# Webasto_X250_3.net
KiCad netlist of a schematic drawn in EAGLE
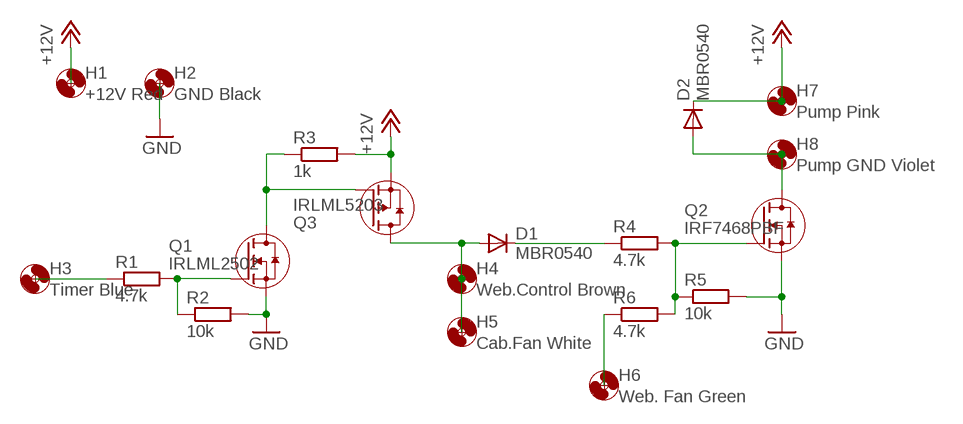
[diagram p0: schematic, sheet 1]

(export (version "E")
  (design (tool "Eeschema 10.0.6"))
  (components
    (comp (ref "D1")
      (value "MBR0540")
      (footprint "eagle-import:SOD-123_MINI-SMA")
      (libsource (lib "eagle-import") (part "CGRM400-G1"))
    )
    (comp (ref "D2")
      (value "MBR0540")
      (footprint "eagle-import:SOD-123_MINI-SMA")
      (libsource (lib "eagle-import") (part "CGRM400-G1"))
    )
    (comp (ref "H1")
      (value "+12V Red")
      (footprint "eagle-import:3,6")
      (libsource (lib "eagle-import") (part "MOUNT-HOLE3.6"))
    )
    (comp (ref "H2")
      (value "GND Black")
      (footprint "eagle-import:3,6")
      (libsource (lib "eagle-import") (part "MOUNT-HOLE3.6"))
    )
    (comp (ref "H3")
      (value "Timer Blue")
      (footprint "eagle-import:3,6")
      (libsource (lib "eagle-import") (part "MOUNT-HOLE3.6"))
    )
    (comp (ref "H4")
      (value "Web.Control Brown")
      (footprint "eagle-import:3,6")
      (libsource (lib "eagle-import") (part "MOUNT-HOLE3.6"))
    )
    (comp (ref "H5")
      (value "Cab.Fan White")
      (footprint "eagle-import:3,6")
      (libsource (lib "eagle-import") (part "MOUNT-HOLE3.6"))
    )
    (comp (ref "H6")
      (value "Web. Fan Green")
      (footprint "eagle-import:3,6")
      (libsource (lib "eagle-import") (part "MOUNT-HOLE3.6"))
    )
    (comp (ref "H7")
      (value "Pump Pink")
      (footprint "eagle-import:3,6")
      (libsource (lib "eagle-import") (part "MOUNT-HOLE3.6"))
    )
    (comp (ref "H8")
      (value "Pump GND Violet")
      (footprint "eagle-import:3,6")
      (libsource (lib "eagle-import") (part "MOUNT-HOLE3.6"))
    )
    (comp (ref "Q1")
      (value "IRLML2502")
      (footprint "eagle-import:SOT-23-GSD")
      (libsource (lib "eagle-import") (part "SI2302"))
    )
    (comp (ref "Q2")
      (value "IRF7468PBF")
      (footprint "eagle-import:SO08")
      (libsource (lib "eagle-import") (part "IRF7468PBF"))
    )
    (comp (ref "Q3")
      (value "IRLML5203")
      (footprint "eagle-import:SOT-23-GSD")
      (libsource (lib "eagle-import") (part "IRLML5203"))
    )
    (comp (ref "R1")
      (value "4.7k")
      (footprint "eagle-import:R0603")
      (libsource (lib "eagle-import") (part "R-EU_R0603"))
    )
    (comp (ref "R2")
      (value "10k")
      (footprint "eagle-import:R0603")
      (libsource (lib "eagle-import") (part "R-EU_R0603"))
    )
    (comp (ref "R3")
      (value "1k")
      (footprint "eagle-import:R0603")
      (libsource (lib "eagle-import") (part "R-EU_R0603"))
    )
    (comp (ref "R4")
      (value "4.7k")
      (footprint "eagle-import:R0603")
      (libsource (lib "eagle-import") (part "R-EU_R0603"))
    )
    (comp (ref "R5")
      (value "10k")
      (footprint "eagle-import:R0603")
      (libsource (lib "eagle-import") (part "R-EU_R0603"))
    )
    (comp (ref "R6")
      (value "4.7k")
      (footprint "eagle-import:R0603")
      (libsource (lib "eagle-import") (part "R-EU_R0603"))
    )
  )
  (nets
    (net (code "1") (name "+12V") (class "Default")
      (node (ref "D2") (pin "C") (pinfunction "C_C") (pintype "passive"))
      (node (ref "H1") (pin "P$1") (pinfunction "P$1_P$1") (pintype "bidirectional"))
      (node (ref "H7") (pin "P$1") (pinfunction "P$1_P$1") (pintype "bidirectional"))
      (node (ref "Q3") (pin "S") (pinfunction "S_S") (pintype "passive"))
      (node (ref "R3") (pin "2") (pinfunction "2_2") (pintype "passive"))
    )
    (net (code "2") (name "GND") (class "Default")
      (node (ref "H2") (pin "P$1") (pinfunction "P$1_P$1") (pintype "bidirectional"))
      (node (ref "Q1") (pin "S") (pinfunction "S_S") (pintype "passive"))
      (node (ref "Q2") (pin "1") (pinfunction "S_1") (pintype "passive"))
      (node (ref "Q2") (pin "2") (pinfunction "S_2") (pintype "passive"))
      (node (ref "Q2") (pin "3") (pinfunction "S_3") (pintype "passive"))
      (node (ref "R2") (pin "2") (pinfunction "2_2") (pintype "passive"))
      (node (ref "R5") (pin "2") (pinfunction "2_2") (pintype "passive"))
    )
    (net (code "3") (name "Net-(D1-PadA)") (class "Default")
      (node (ref "D1") (pin "A") (pinfunction "A_A") (pintype "passive"))
      (node (ref "H4") (pin "P$1") (pinfunction "P$1_P$1") (pintype "bidirectional"))
      (node (ref "H5") (pin "P$1") (pinfunction "P$1_P$1") (pintype "bidirectional"))
      (node (ref "Q3") (pin "D") (pinfunction "D_D") (pintype "passive"))
    )
    (net (code "4") (name "Net-(D1-PadC)") (class "Default")
      (node (ref "D1") (pin "C") (pinfunction "C_C") (pintype "passive"))
      (node (ref "R4") (pin "1") (pinfunction "1_1") (pintype "passive"))
    )
    (net (code "5") (name "Net-(D2-PadA)") (class "Default")
      (node (ref "D2") (pin "A") (pinfunction "A_A") (pintype "passive"))
      (node (ref "H8") (pin "P$1") (pinfunction "P$1_P$1") (pintype "bidirectional"))
      (node (ref "Q2") (pin "5") (pinfunction "D_5") (pintype "passive"))
      (node (ref "Q2") (pin "6") (pinfunction "D_6") (pintype "passive"))
      (node (ref "Q2") (pin "7") (pinfunction "D_7") (pintype "passive"))
      (node (ref "Q2") (pin "8") (pinfunction "D_8") (pintype "passive"))
    )
    (net (code "6") (name "Net-(H3-PadP$1)") (class "Default")
      (node (ref "H3") (pin "P$1") (pinfunction "P$1_P$1") (pintype "bidirectional"))
      (node (ref "R1") (pin "1") (pinfunction "1_1") (pintype "passive"))
    )
    (net (code "7") (name "Net-(H6-PadP$1)") (class "Default")
      (node (ref "H6") (pin "P$1") (pinfunction "P$1_P$1") (pintype "bidirectional"))
      (node (ref "R6") (pin "1") (pinfunction "1_1") (pintype "passive"))
    )
    (net (code "8") (name "Net-(Q1-PadD)") (class "Default")
      (node (ref "Q1") (pin "D") (pinfunction "D_D") (pintype "passive"))
      (node (ref "Q3") (pin "G") (pinfunction "G_G") (pintype "passive"))
      (node (ref "R3") (pin "1") (pinfunction "1_1") (pintype "passive"))
    )
    (net (code "9") (name "Net-(Q1-PadG)") (class "Default")
      (node (ref "Q1") (pin "G") (pinfunction "G_G") (pintype "passive"))
      (node (ref "R1") (pin "2") (pinfunction "2_2") (pintype "passive"))
      (node (ref "R2") (pin "1") (pinfunction "1_1") (pintype "passive"))
    )
    (net (code "10") (name "Net-(Q2-G)") (class "Default")
      (node (ref "Q2") (pin "4") (pinfunction "G_4") (pintype "passive"))
      (node (ref "R4") (pin "2") (pinfunction "2_2") (pintype "passive"))
      (node (ref "R5") (pin "1") (pinfunction "1_1") (pintype "passive"))
      (node (ref "R6") (pin "2") (pinfunction "2_2") (pintype "passive"))
    )
  )
)
